# BEP2_rev1.net
KiCad netlist of a schematic drawn in EAGLE
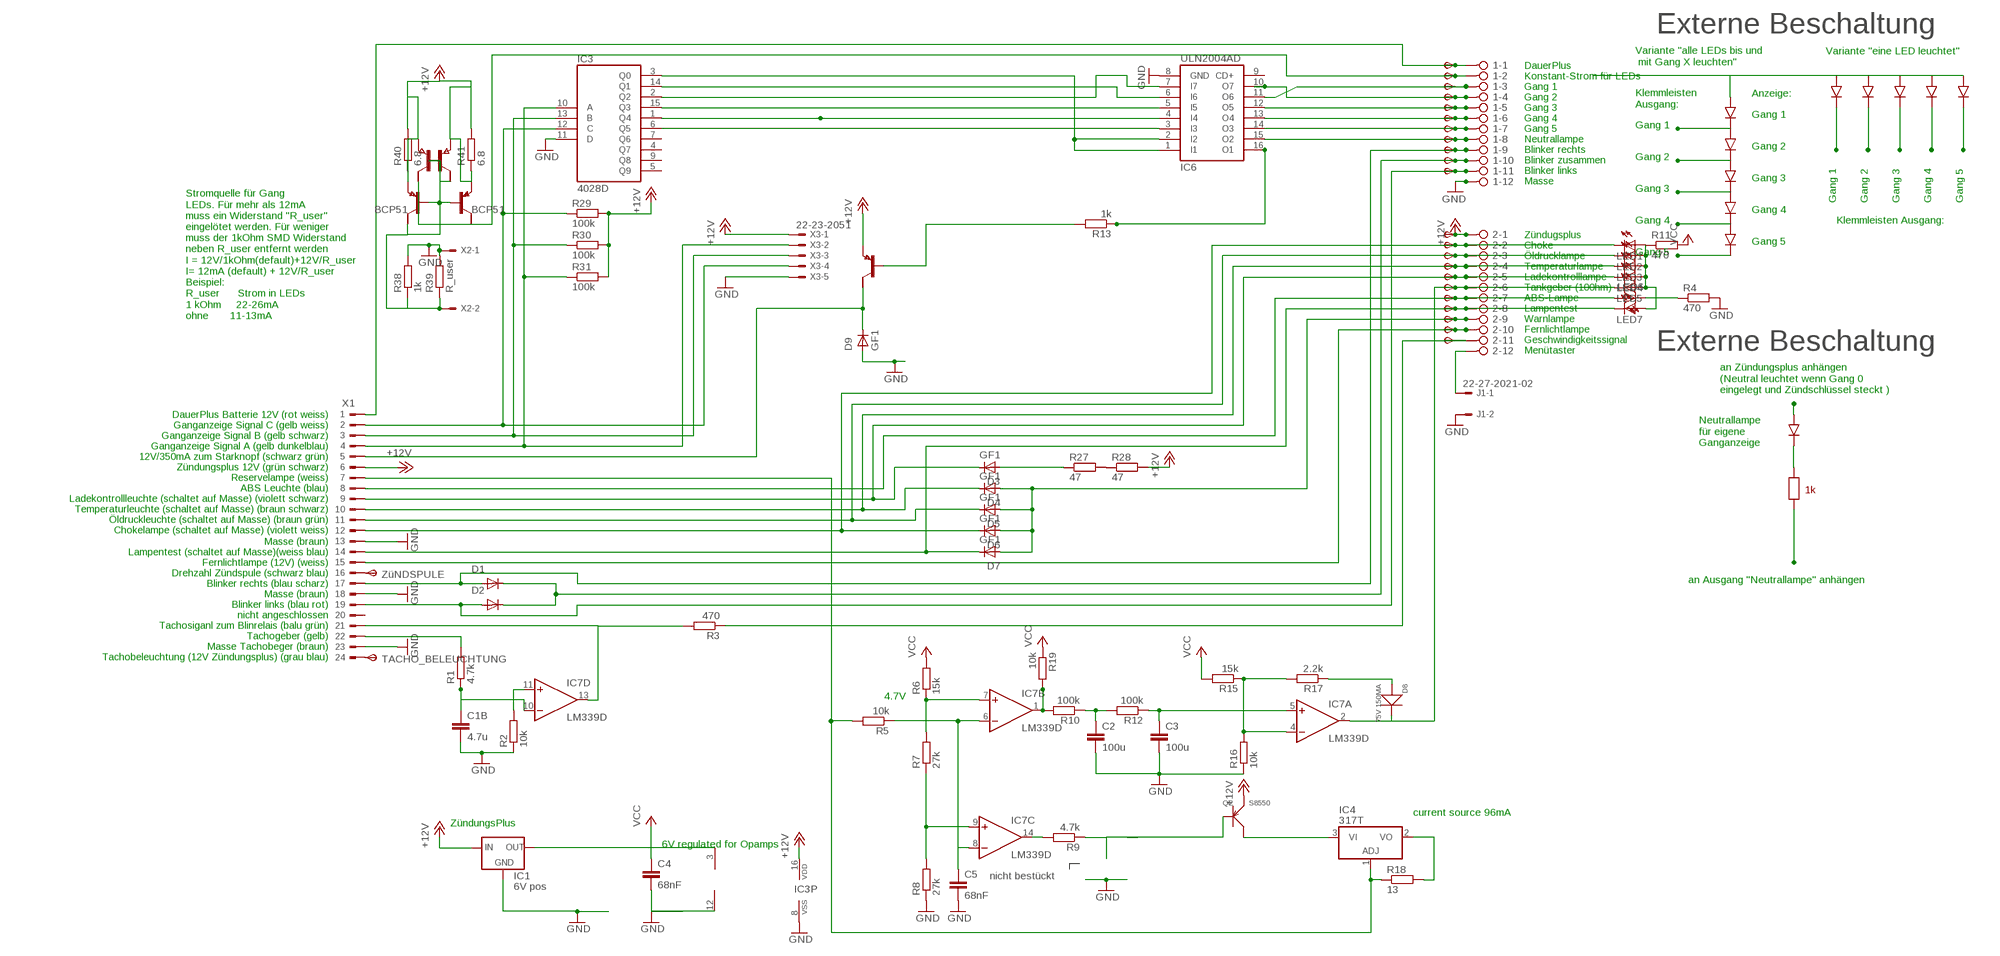
[diagram p0: schematic, sheet 1]

(export (version "E")
  (design (tool "Eeschema 10.0.6"))
  (components
    (comp (ref "1")
      (value "2081-1132")
      (footprint "eagle-import:12-PIN")
      (libsource (lib "eagle-import") (part "2081-1132"))
    )
    (comp (ref "2")
      (value "2081-1132")
      (footprint "eagle-import:12-PIN")
      (libsource (lib "eagle-import") (part "2081-1132"))
    )
    (comp (ref "C1B")
      (value "4.7u")
      (footprint "eagle-import:C0805K")
      (libsource (lib "eagle-import") (part "C-EUC0805K"))
    )
    (comp (ref "C2")
      (value "100u")
      (footprint "eagle-import:C1206K")
      (libsource (lib "eagle-import") (part "C-EUC1206K"))
    )
    (comp (ref "C3")
      (value "100u")
      (footprint "eagle-import:C1206K")
      (libsource (lib "eagle-import") (part "C-EUC1206K"))
    )
    (comp (ref "C4")
      (value "68nF")
      (footprint "eagle-import:C1206K")
      (libsource (lib "eagle-import") (part "C-EUC1206K"))
    )
    (comp (ref "C5")
      (value "68nF")
      (footprint "eagle-import:C1206K")
      (libsource (lib "eagle-import") (part "C-EUC1206K"))
    )
    (comp (ref "D1")
      (value "GF1")
      (footprint "eagle-import:SMA-DO214AC")
      (libsource (lib "eagle-import") (part "GF1"))
    )
    (comp (ref "D2")
      (value "GF1")
      (footprint "eagle-import:SMA-DO214AC")
      (libsource (lib "eagle-import") (part "GF1"))
    )
    (comp (ref "D3")
      (value "GF1")
      (footprint "eagle-import:SMA-DO214AC")
      (libsource (lib "eagle-import") (part "GF1"))
    )
    (comp (ref "D4")
      (value "GF1")
      (footprint "eagle-import:SMA-DO214AC")
      (libsource (lib "eagle-import") (part "GF1"))
    )
    (comp (ref "D5")
      (value "GF1")
      (footprint "eagle-import:SMA-DO214AC")
      (libsource (lib "eagle-import") (part "GF1"))
    )
    (comp (ref "D6")
      (value "GF1")
      (footprint "eagle-import:SMA-DO214AC")
      (libsource (lib "eagle-import") (part "GF1"))
    )
    (comp (ref "D7")
      (value "GF1")
      (footprint "eagle-import:SMA-DO214AC")
      (libsource (lib "eagle-import") (part "GF1"))
    )
    (comp (ref "D8")
      (value "75V 150MA")
      (footprint "eagle-import:LED-1206")
      (fields (field (name "MPN") "CD1206-S01575"))
      (libsource (lib "eagle-import") (part "SMD-DIODE-SWITCHING-75V-150MA(D1206)"))
    )
    (comp (ref "D9")
      (value "GF1")
      (footprint "eagle-import:SMA-DO214AC")
      (libsource (lib "eagle-import") (part "GF1"))
    )
    (comp (ref "IC1")
      (value "6V pos")
      (footprint "eagle-import:78LXX")
      (libsource (lib "eagle-import") (part "78LXX"))
    )
    (comp (ref "IC3")
      (value "4028D")
      (footprint "eagle-import:SO16")
      (libsource (lib "eagle-import") (part "4028D"))
    )
    (comp (ref "IC4")
      (value "317T")
      (footprint "eagle-import:TO220H")
      (libsource (lib "eagle-import") (part "317T"))
    )
    (comp (ref "IC6")
      (value "ULN2004AD")
      (footprint "eagle-import:SO16")
      (libsource (lib "eagle-import") (part "ULN2004AD"))
    )
    (comp (ref "IC7")
      (value "LM339D")
      (footprint "eagle-import:SO14")
      (libsource (lib "eagle-import") (part "LM339D"))
    )
    (comp (ref "J1")
      (value "22-27-2021-02")
      (footprint "eagle-import:6410-02")
      (libsource (lib "eagle-import") (part "22-?-0227-2021"))
    )
    (comp (ref "LED1")
      (value "LEDLD260")
      (footprint "eagle-import:LD260")
      (libsource (lib "eagle-import") (part "LEDLD260"))
    )
    (comp (ref "LED2")
      (value "LEDLD260")
      (footprint "eagle-import:LD260")
      (libsource (lib "eagle-import") (part "LEDLD260"))
    )
    (comp (ref "LED3")
      (value "LEDLD260")
      (footprint "eagle-import:LD260")
      (libsource (lib "eagle-import") (part "LEDLD260"))
    )
    (comp (ref "LED4")
      (value "LEDLD260")
      (footprint "eagle-import:LD260")
      (libsource (lib "eagle-import") (part "LEDLD260"))
    )
    (comp (ref "LED5")
      (value "LEDLD260")
      (footprint "eagle-import:LD260")
      (libsource (lib "eagle-import") (part "LEDLD260"))
    )
    (comp (ref "LED6")
      (value "LEDLD260")
      (footprint "eagle-import:LD260")
      (libsource (lib "eagle-import") (part "LEDLD260"))
    )
    (comp (ref "LED7")
      (value "LEDLD260")
      (footprint "eagle-import:LD260")
      (libsource (lib "eagle-import") (part "LEDLD260"))
    )
    (comp (ref "Q2")
      (value "S8550")
      (footprint "eagle-import:SOT-23")
      (libsource (lib "eagle-import") (part "SMD-TRANSISTORS-PNP-25V-500MA-S8550(SOT-23)"))
    )
    (comp (ref "Q3")
      (value "BCP53T1")
      (footprint "eagle-import:SOT223")
      (libsource (lib "eagle-import") (part "BCP53T1"))
    )
    (comp (ref "R1")
      (value "4.7k")
      (footprint "eagle-import:R0805")
      (libsource (lib "eagle-import") (part "R-EU_R0805"))
    )
    (comp (ref "R2")
      (value "10k")
      (footprint "eagle-import:R0805")
      (libsource (lib "eagle-import") (part "R-EU_R0805"))
    )
    (comp (ref "R3")
      (value "470")
      (footprint "eagle-import:R0805")
      (libsource (lib "eagle-import") (part "R-EU_R0805"))
    )
    (comp (ref "R4")
      (value "470")
      (footprint "eagle-import:R0805")
      (libsource (lib "eagle-import") (part "R-EU_R0805"))
    )
    (comp (ref "R5")
      (value "10k")
      (footprint "eagle-import:R0805")
      (libsource (lib "eagle-import") (part "R-EU_R0805"))
    )
    (comp (ref "R6")
      (value "15k")
      (footprint "eagle-import:R0805")
      (libsource (lib "eagle-import") (part "R-EU_R0805"))
    )
    (comp (ref "R7")
      (value "27k")
      (footprint "eagle-import:R0805")
      (libsource (lib "eagle-import") (part "R-EU_R0805"))
    )
    (comp (ref "R8")
      (value "27k")
      (footprint "eagle-import:R0805")
      (libsource (lib "eagle-import") (part "R-EU_R0805"))
    )
    (comp (ref "R9")
      (value "4.7k")
      (footprint "eagle-import:R0805")
      (libsource (lib "eagle-import") (part "R-EU_R0805"))
    )
    (comp (ref "R10")
      (value "100k")
      (footprint "eagle-import:R0805")
      (libsource (lib "eagle-import") (part "R-EU_R0805"))
    )
    (comp (ref "R11")
      (value "470")
      (footprint "eagle-import:R0805")
      (libsource (lib "eagle-import") (part "R-EU_R0805"))
    )
    (comp (ref "R12")
      (value "100k")
      (footprint "eagle-import:R0805")
      (libsource (lib "eagle-import") (part "R-EU_R0805"))
    )
    (comp (ref "R13")
      (value "1k")
      (footprint "eagle-import:R0805")
      (libsource (lib "eagle-import") (part "R-EU_R0805"))
    )
    (comp (ref "R15")
      (value "15k")
      (footprint "eagle-import:R0805")
      (libsource (lib "eagle-import") (part "R-EU_R0805"))
    )
    (comp (ref "R16")
      (value "10k")
      (footprint "eagle-import:R0805")
      (libsource (lib "eagle-import") (part "R-EU_R0805"))
    )
    (comp (ref "R17")
      (value "2.2k")
      (footprint "eagle-import:R0805")
      (libsource (lib "eagle-import") (part "R-EU_R0805"))
    )
    (comp (ref "R18")
      (value "13")
      (footprint "eagle-import:R1206")
      (libsource (lib "eagle-import") (part "R-EU_R1206"))
    )
    (comp (ref "R19")
      (value "10k")
      (footprint "eagle-import:R0805")
      (libsource (lib "eagle-import") (part "R-EU_R0805"))
    )
    (comp (ref "R27")
      (value "47")
      (footprint "eagle-import:V235_17_1MM")
      (libsource (lib "eagle-import") (part "R-EU_V235/17_1MM"))
    )
    (comp (ref "R28")
      (value "47")
      (footprint "eagle-import:V235_17_1MM")
      (libsource (lib "eagle-import") (part "R-EU_V235/17_1MM"))
    )
    (comp (ref "R29")
      (value "100k")
      (footprint "eagle-import:R0805")
      (libsource (lib "eagle-import") (part "R-EU_R0805"))
    )
    (comp (ref "R30")
      (value "100k")
      (footprint "eagle-import:R0805")
      (libsource (lib "eagle-import") (part "R-EU_R0805"))
    )
    (comp (ref "R31")
      (value "100k")
      (footprint "eagle-import:R0805")
      (libsource (lib "eagle-import") (part "R-EU_R0805"))
    )
    (comp (ref "R38")
      (value "1k")
      (footprint "eagle-import:R0805")
      (libsource (lib "eagle-import") (part "R-EU_R0805"))
    )
    (comp (ref "R39")
      (value "R_user")
      (footprint "eagle-import:R0805")
      (libsource (lib "eagle-import") (part "R-EU_R0805"))
    )
    (comp (ref "R40")
      (value "6.8")
      (footprint "eagle-import:R0805")
      (libsource (lib "eagle-import") (part "R-EU_R0805"))
    )
    (comp (ref "R41")
      (value "6.8")
      (footprint "eagle-import:R0805")
      (libsource (lib "eagle-import") (part "R-EU_R0805"))
    )
    (comp (ref "T1")
      (value "PNP2SM8")
      (footprint "eagle-import:SM8")
      (libsource (lib "eagle-import") (part "PNP2SM8"))
    )
    (comp (ref "T13")
      (value "BCP53T1")
      (footprint "eagle-import:SOT223")
      (fields (field (name "T") "BCP51"))
      (libsource (lib "eagle-import") (part "BCP53T1"))
    )
    (comp (ref "T14")
      (value "BCP53T1")
      (footprint "eagle-import:SOT223")
      (fields (field (name "T") "BCP51"))
      (libsource (lib "eagle-import") (part "BCP53T1"))
    )
    (comp (ref "TACHO_BELEUCHTUNG")
      (value "TPSP1_1MM")
      (footprint "eagle-import:P1_1.0MM")
      (libsource (lib "eagle-import") (part "TPSP1_1MM"))
    )
    (comp (ref "TP1")
      (value "TPSB1,27")
      (footprint "eagle-import:B1,27")
      (libsource (lib "eagle-import") (part "TPSB1,27"))
    )
    (comp (ref "TP2")
      (value "TPSB1,27")
      (footprint "eagle-import:B1,27")
      (libsource (lib "eagle-import") (part "TPSB1,27"))
    )
    (comp (ref "TP3")
      (value "TPSB1,27")
      (footprint "eagle-import:B1,27")
      (libsource (lib "eagle-import") (part "TPSB1,27"))
    )
    (comp (ref "TP4")
      (value "TPSB1,27")
      (footprint "eagle-import:B1,27")
      (libsource (lib "eagle-import") (part "TPSB1,27"))
    )
    (comp (ref "TP5")
      (value "TPSB1,27")
      (footprint "eagle-import:B1,27")
      (libsource (lib "eagle-import") (part "TPSB1,27"))
    )
    (comp (ref "TP6")
      (value "TPSB1,27")
      (footprint "eagle-import:B1,27")
      (libsource (lib "eagle-import") (part "TPSB1,27"))
    )
    (comp (ref "TP7")
      (value "TPSB1,27")
      (footprint "eagle-import:B1,27")
      (libsource (lib "eagle-import") (part "TPSB1,27"))
    )
    (comp (ref "TP8")
      (value "TPSB1,27")
      (footprint "eagle-import:B1,27")
      (libsource (lib "eagle-import") (part "TPSB1,27"))
    )
    (comp (ref "TP9")
      (value "TPSB1,27")
      (footprint "eagle-import:B1,27")
      (libsource (lib "eagle-import") (part "TPSB1,27"))
    )
    (comp (ref "TP10")
      (value "TPSB1,27")
      (footprint "eagle-import:B1,27")
      (libsource (lib "eagle-import") (part "TPSB1,27"))
    )
    (comp (ref "TP11")
      (value "TPSB1,27")
      (footprint "eagle-import:B1,27")
      (libsource (lib "eagle-import") (part "TPSB1,27"))
    )
    (comp (ref "TP12")
      (value "TPSB1,27")
      (footprint "eagle-import:B1,27")
      (libsource (lib "eagle-import") (part "TPSB1,27"))
    )
    (comp (ref "TP16")
      (value "TPSB1,27")
      (footprint "eagle-import:B1,27")
      (libsource (lib "eagle-import") (part "TPSB1,27"))
    )
    (comp (ref "TP17")
      (value "TPSB1,27")
      (footprint "eagle-import:B1,27")
      (libsource (lib "eagle-import") (part "TPSB1,27"))
    )
    (comp (ref "TP18")
      (value "TPSB1,27")
      (footprint "eagle-import:B1,27")
      (libsource (lib "eagle-import") (part "TPSB1,27"))
    )
    (comp (ref "TP19")
      (value "TPSB1,27")
      (footprint "eagle-import:B1,27")
      (libsource (lib "eagle-import") (part "TPSB1,27"))
    )
    (comp (ref "TP21")
      (value "TPSB1,27")
      (footprint "eagle-import:B1,27")
      (libsource (lib "eagle-import") (part "TPSB1,27"))
    )
    (comp (ref "TP22")
      (value "TPSB1,27")
      (footprint "eagle-import:B1,27")
      (libsource (lib "eagle-import") (part "TPSB1,27"))
    )
    (comp (ref "TP23")
      (value "TPSB1,27")
      (footprint "eagle-import:B1,27")
      (libsource (lib "eagle-import") (part "TPSB1,27"))
    )
    (comp (ref "TP24")
      (value "TPSB1,27")
      (footprint "eagle-import:B1,27")
      (libsource (lib "eagle-import") (part "TPSB1,27"))
    )
    (comp (ref "TP25")
      (value "TPSB1,27")
      (footprint "eagle-import:B1,27")
      (libsource (lib "eagle-import") (part "TPSB1,27"))
    )
    (comp (ref "TP26")
      (value "TPSB1,27")
      (footprint "eagle-import:B1,27")
      (libsource (lib "eagle-import") (part "TPSB1,27"))
    )
    (comp (ref "X1")
      (value "CON_BMW")
      (footprint "eagle-import:24-PIN")
      (libsource (lib "eagle-import") (part "CON_BMW"))
    )
    (comp (ref "X2")
      (value "22-23-2021")
      (footprint "eagle-import:22-23-2021")
      (fields (field (name "MF") "MOLEX"))
      (libsource (lib "eagle-import") (part "22-23-2021"))
    )
    (comp (ref "X3")
      (value "22-23-2051")
      (footprint "eagle-import:22-23-2051")
      (fields (field (name "MF") "MOLEX"))
      (libsource (lib "eagle-import") (part "22-23-2051"))
    )
    (comp (ref "ZüNDSPULE")
      (value "TPSP1_1MM")
      (footprint "eagle-import:P1_1.0MM")
      (libsource (lib "eagle-import") (part "TPSP1_1MM"))
    )
  )
  (nets
    (net (code "1") (name "+12V") (class "Default")
      (node (ref "2") (pin "1") (pinfunction "KL_1") (pintype "passive"))
      (node (ref "IC1") (pin "IN") (pinfunction "IN_IN") (pintype "input"))
      (node (ref "IC3") (pin "16") (pinfunction "VDD_16") (pintype "power_in"))
      (node (ref "Q2") (pin "2") (pinfunction "E_2") (pintype "passive"))
      (node (ref "Q3") (pin "3") (pinfunction "E_3") (pintype "passive"))
      (node (ref "R28") (pin "2") (pinfunction "2_2") (pintype "passive"))
      (node (ref "R29") (pin "2") (pinfunction "2_2") (pintype "passive"))
      (node (ref "R30") (pin "2") (pinfunction "2_2") (pintype "passive"))
      (node (ref "R31") (pin "2") (pinfunction "2_2") (pintype "passive"))
      (node (ref "R40") (pin "1") (pinfunction "1_1") (pintype "passive"))
      (node (ref "R40") (pin "2") (pinfunction "2_2") (pintype "passive"))
      (node (ref "R41") (pin "1") (pinfunction "1_1") (pintype "passive"))
      (node (ref "R41") (pin "2") (pinfunction "2_2") (pintype "passive"))
      (node (ref "T1") (pin "1") (pinfunction "E_1") (pintype "passive"))
      (node (ref "T1") (pin "3") (pinfunction "E_3") (pintype "passive"))
      (node (ref "T13") (pin "3") (pinfunction "E_3") (pintype "passive"))
      (node (ref "T14") (pin "3") (pinfunction "E_3") (pintype "passive"))
      (node (ref "TP12") (pin "TP") (pinfunction "PP_TP") (pintype "input"))
      (node (ref "X1") (pin "6") (pinfunction "6_6") (pintype "passive"))
      (node (ref "X3") (pin "1") (pinfunction "S_1") (pintype "passive"))
    )
    (net (code "2") (name "GND") (class "Default")
      (node (ref "1") (pin "12") (pinfunction "KL_12") (pintype "passive"))
      (node (ref "C1B") (pin "2") (pinfunction "2_2") (pintype "passive"))
      (node (ref "C2") (pin "2") (pinfunction "2_2") (pintype "passive"))
      (node (ref "C3") (pin "2") (pinfunction "2_2") (pintype "passive"))
      (node (ref "C4") (pin "2") (pinfunction "2_2") (pintype "passive"))
      (node (ref "C5") (pin "2") (pinfunction "2_2") (pintype "passive"))
      (node (ref "D9") (pin "A") (pinfunction "A_A") (pintype "passive"))
      (node (ref "IC1") (pin "GND") (pinfunction "GND_GND") (pintype "input"))
      (node (ref "IC3") (pin "11") (pinfunction "D_11") (pintype "input"))
      (node (ref "IC3") (pin "8") (pinfunction "VSS_8") (pintype "power_in"))
      (node (ref "IC6") (pin "8") (pinfunction "GND_8") (pintype "power_in"))
      (node (ref "IC7") (pin "12") (pinfunction "GND_12") (pintype "power_in"))
      (node (ref "J1") (pin "2") (pinfunction "S_2") (pintype "passive"))
      (node (ref "R16") (pin "1") (pinfunction "1_1") (pintype "passive"))
      (node (ref "R2") (pin "1") (pinfunction "1_1") (pintype "passive"))
      (node (ref "R38") (pin "2") (pinfunction "2_2") (pintype "passive"))
      (node (ref "R39") (pin "2") (pinfunction "2_2") (pintype "passive"))
      (node (ref "R4") (pin "2") (pinfunction "2_2") (pintype "passive"))
      (node (ref "R8") (pin "1") (pinfunction "1_1") (pintype "passive"))
      (node (ref "X1") (pin "13") (pinfunction "13_13") (pintype "passive"))
      (node (ref "X1") (pin "18") (pinfunction "18_18") (pintype "passive"))
      (node (ref "X1") (pin "23") (pinfunction "23_23") (pintype "passive"))
      (node (ref "X2") (pin "1") (pinfunction "S_1") (pintype "passive"))
      (node (ref "X3") (pin "5") (pinfunction "S_5") (pintype "passive"))
    )
    (net (code "3") (name "Net-(1A-KL)") (class "Default")
      (node (ref "1") (pin "1") (pinfunction "KL_1") (pintype "passive"))
      (node (ref "TP1") (pin "TP") (pinfunction "PP_TP") (pintype "input"))
      (node (ref "X1") (pin "1") (pinfunction "1_1") (pintype "passive"))
    )
    (net (code "4") (name "Net-(1B-KL)") (class "Default")
      (node (ref "1") (pin "10") (pinfunction "KL_10") (pintype "passive"))
      (node (ref "D1") (pin "K") (pinfunction "C_K") (pintype "passive"))
      (node (ref "D2") (pin "K") (pinfunction "C_K") (pintype "passive"))
      (node (ref "TP10") (pin "TP") (pinfunction "PP_TP") (pintype "input"))
    )
    (net (code "5") (name "Net-(1C-KL)") (class "Default")
      (node (ref "1") (pin "11") (pinfunction "KL_11") (pintype "passive"))
      (node (ref "D2") (pin "A") (pinfunction "A_A") (pintype "passive"))
      (node (ref "TP11") (pin "TP") (pinfunction "PP_TP") (pintype "input"))
      (node (ref "X1") (pin "19") (pinfunction "19_19") (pintype "passive"))
    )
    (net (code "6") (name "Net-(1E-KL)") (class "Default")
      (node (ref "1") (pin "2") (pinfunction "KL_2") (pintype "passive"))
      (node (ref "T1") (pin "8") (pinfunction "C1_8") (pintype "passive"))
      (node (ref "T14") (pin "2") (pinfunction "C_2") (pintype "passive"))
      (node (ref "TP2") (pin "TP") (pinfunction "PP_TP") (pintype "input"))
    )
    (net (code "7") (name "Net-(1F-KL)") (class "Default")
      (node (ref "1") (pin "3") (pinfunction "KL_3") (pintype "passive"))
      (node (ref "IC6") (pin "11") (pinfunction "O6_11") (pintype "open_collector"))
      (node (ref "TP3") (pin "TP") (pinfunction "PP_TP") (pintype "input"))
    )
    (net (code "8") (name "Net-(1G-KL)") (class "Default")
      (node (ref "1") (pin "4") (pinfunction "KL_4") (pintype "passive"))
      (node (ref "IC6") (pin "10") (pinfunction "O7_10") (pintype "open_collector"))
      (node (ref "TP4") (pin "TP") (pinfunction "PP_TP") (pintype "input"))
    )
    (net (code "9") (name "Net-(1H-KL)") (class "Default")
      (node (ref "1") (pin "5") (pinfunction "KL_5") (pintype "passive"))
      (node (ref "IC6") (pin "12") (pinfunction "O5_12") (pintype "open_collector"))
      (node (ref "TP5") (pin "TP") (pinfunction "PP_TP") (pintype "input"))
    )
    (net (code "10") (name "Net-(1I-KL)") (class "Default")
      (node (ref "1") (pin "6") (pinfunction "KL_6") (pintype "passive"))
      (node (ref "IC6") (pin "13") (pinfunction "O4_13") (pintype "open_collector"))
      (node (ref "TP6") (pin "TP") (pinfunction "PP_TP") (pintype "input"))
    )
    (net (code "11") (name "Net-(1J-KL)") (class "Default")
      (node (ref "1") (pin "7") (pinfunction "KL_7") (pintype "passive"))
      (node (ref "IC6") (pin "14") (pinfunction "O3_14") (pintype "open_collector"))
      (node (ref "TP7") (pin "TP") (pinfunction "PP_TP") (pintype "input"))
    )
    (net (code "12") (name "Net-(1K-KL)") (class "Default")
      (node (ref "1") (pin "8") (pinfunction "KL_8") (pintype "passive"))
      (node (ref "IC6") (pin "15") (pinfunction "O2_15") (pintype "open_collector"))
      (node (ref "TP8") (pin "TP") (pinfunction "PP_TP") (pintype "input"))
    )
    (net (code "13") (name "Net-(1L-KL)") (class "Default")
      (node (ref "1") (pin "9") (pinfunction "KL_9") (pintype "passive"))
      (node (ref "D1") (pin "A") (pinfunction "A_A") (pintype "passive"))
      (node (ref "TP9") (pin "TP") (pinfunction "PP_TP") (pintype "input"))
      (node (ref "X1") (pin "17") (pinfunction "17_17") (pintype "passive"))
    )
    (net (code "14") (name "Net-(2B-KL)") (class "Default")
      (node (ref "2") (pin "10") (pinfunction "KL_10") (pintype "passive"))
      (node (ref "TP25") (pin "TP") (pinfunction "PP_TP") (pintype "input"))
      (node (ref "X1") (pin "15") (pinfunction "15_15") (pintype "passive"))
    )
    (net (code "15") (name "Net-(2C-KL)") (class "Default")
      (node (ref "2") (pin "11") (pinfunction "KL_11") (pintype "passive"))
      (node (ref "R3") (pin "1") (pinfunction "1_1") (pintype "passive"))
      (node (ref "TP26") (pin "TP") (pinfunction "PP_TP") (pintype "input"))
    )
    (net (code "16") (name "Net-(2D-KL)") (class "Default")
      (node (ref "2") (pin "12") (pinfunction "KL_12") (pintype "passive"))
      (node (ref "J1") (pin "1") (pinfunction "S_1") (pintype "passive"))
    )
    (net (code "17") (name "Net-(2E-KL)") (class "Default")
      (node (ref "2") (pin "2") (pinfunction "KL_2") (pintype "passive"))
      (node (ref "D6") (pin "K") (pinfunction "C_K") (pintype "passive"))
      (node (ref "LED1") (pin "K") (pinfunction "C_K") (pintype "passive"))
      (node (ref "TP16") (pin "TP") (pinfunction "PP_TP") (pintype "input"))
      (node (ref "X1") (pin "12") (pinfunction "12_12") (pintype "passive"))
    )
    (net (code "18") (name "Net-(2F-KL)") (class "Default")
      (node (ref "2") (pin "3") (pinfunction "KL_3") (pintype "passive"))
      (node (ref "D5") (pin "K") (pinfunction "C_K") (pintype "passive"))
      (node (ref "LED2") (pin "K") (pinfunction "C_K") (pintype "passive"))
      (node (ref "TP17") (pin "TP") (pinfunction "PP_TP") (pintype "input"))
      (node (ref "X1") (pin "11") (pinfunction "11_11") (pintype "passive"))
    )
    (net (code "19") (name "Net-(2G-KL)") (class "Default")
      (node (ref "2") (pin "4") (pinfunction "KL_4") (pintype "passive"))
      (node (ref "D4") (pin "K") (pinfunction "C_K") (pintype "passive"))
      (node (ref "LED3") (pin "K") (pinfunction "C_K") (pintype "passive"))
      (node (ref "TP18") (pin "TP") (pinfunction "PP_TP") (pintype "input"))
      (node (ref "X1") (pin "10") (pinfunction "10_10") (pintype "passive"))
    )
    (net (code "20") (name "Net-(2H-KL)") (class "Default")
      (node (ref "2") (pin "5") (pinfunction "KL_5") (pintype "passive"))
      (node (ref "D3") (pin "K") (pinfunction "C_K") (pintype "passive"))
      (node (ref "LED4") (pin "K") (pinfunction "C_K") (pintype "passive"))
      (node (ref "TP19") (pin "TP") (pinfunction "PP_TP") (pintype "input"))
      (node (ref "X1") (pin "9") (pinfunction "9_9") (pintype "passive"))
    )
    (net (code "21") (name "Net-(2I-KL)") (class "Default")
      (node (ref "2") (pin "6") (pinfunction "KL_6") (pintype "passive"))
      (node (ref "D8") (pin "-") (pinfunction "-_-") (pintype "passive"))
      (node (ref "IC7") (pin "2") (pinfunction "OUT_2") (pintype "open_collector"))
      (node (ref "LED5") (pin "K") (pinfunction "C_K") (pintype "passive"))
      (node (ref "TP21") (pin "TP") (pinfunction "PP_TP") (pintype "input"))
    )
    (net (code "22") (name "Net-(2J-KL)") (class "Default")
      (node (ref "2") (pin "7") (pinfunction "KL_7") (pintype "passive"))
      (node (ref "LED6") (pin "A") (pinfunction "A_A") (pintype "passive"))
      (node (ref "TP22") (pin "TP") (pinfunction "PP_TP") (pintype "input"))
      (node (ref "X1") (pin "8") (pinfunction "8_8") (pintype "passive"))
    )
    (net (code "23") (name "Net-(2K-KL)") (class "Default")
      (node (ref "2") (pin "8") (pinfunction "KL_8") (pintype "passive"))
      (node (ref "D7") (pin "K") (pinfunction "C_K") (pintype "passive"))
      (node (ref "LED7") (pin "K") (pinfunction "C_K") (pintype "passive"))
      (node (ref "TP23") (pin "TP") (pinfunction "PP_TP") (pintype "input"))
      (node (ref "X1") (pin "14") (pinfunction "14_14") (pintype "passive"))
    )
    (net (code "24") (name "Net-(2L-KL)") (class "Default")
      (node (ref "2") (pin "9") (pinfunction "KL_9") (pintype "passive"))
      (node (ref "D4") (pin "A") (pinfunction "A_A") (pintype "passive"))
      (node (ref "D5") (pin "A") (pinfunction "A_A") (pintype "passive"))
      (node (ref "D6") (pin "A") (pinfunction "A_A") (pintype "passive"))
      (node (ref "D7") (pin "A") (pinfunction "A_A") (pintype "passive"))
      (node (ref "TP24") (pin "TP") (pinfunction "PP_TP") (pintype "input"))
    )
    (net (code "25") (name "Net-(C2-Pad1)") (class "Default")
      (node (ref "C2") (pin "1") (pinfunction "1_1") (pintype "passive"))
      (node (ref "R10") (pin "1") (pinfunction "1_1") (pintype "passive"))
      (node (ref "R12") (pin "2") (pinfunction "2_2") (pintype "passive"))
    )
    (net (code "26") (name "Net-(D3-PadA)") (class "Default")
      (node (ref "D3") (pin "A") (pinfunction "A_A") (pintype "passive"))
      (node (ref "R27") (pin "1") (pinfunction "1_1") (pintype "passive"))
    )
    (net (code "27") (name "Net-(D8-Pad+)") (class "Default")
      (node (ref "D8") (pin "+") (pinfunction "+_+") (pintype "passive"))
      (node (ref "R17") (pin "1") (pinfunction "1_1") (pintype "passive"))
    )
    (net (code "28") (name "Net-(D9-C)") (class "Default")
      (node (ref "D9") (pin "K") (pinfunction "C_K") (pintype "passive"))
      (node (ref "Q3") (pin "2") (pinfunction "C_2") (pintype "passive"))
      (node (ref "X1") (pin "5") (pinfunction "5_5") (pintype "passive"))
    )
    (net (code "29") (name "Net-(IC3A-A)") (class "Default")
      (node (ref "IC3") (pin "10") (pinfunction "A_10") (pintype "input"))
      (node (ref "R31") (pin "1") (pinfunction "1_1") (pintype "passive"))
      (node (ref "X1") (pin "4") (pinfunction "4_4") (pintype "passive"))
      (node (ref "X3") (pin "2") (pinfunction "S_2") (pintype "passive"))
    )
    (net (code "30") (name "Net-(IC3A-B)") (class "Default")
      (node (ref "IC3") (pin "13") (pinfunction "B_13") (pintype "input"))
      (node (ref "R30") (pin "1") (pinfunction "1_1") (pintype "passive"))
      (node (ref "X1") (pin "3") (pinfunction "3_3") (pintype "passive"))
      (node (ref "X3") (pin "3") (pinfunction "S_3") (pintype "passive"))
    )
    (net (code "31") (name "Net-(IC3A-C)") (class "Default")
      (node (ref "IC3") (pin "12") (pinfunction "C_12") (pintype "input"))
      (node (ref "R29") (pin "1") (pinfunction "1_1") (pintype "passive"))
      (node (ref "X1") (pin "2") (pinfunction "2_2") (pintype "passive"))
      (node (ref "X3") (pin "4") (pinfunction "S_4") (pintype "passive"))
    )
    (net (code "32") (name "Net-(IC3A-Q0)") (class "Default")
      (node (ref "IC3") (pin "3") (pinfunction "Q0_3") (pintype "output"))
      (node (ref "IC6") (pin "1") (pinfunction "I1_1") (pintype "input"))
      (node (ref "IC6") (pin "2") (pinfunction "I2_2") (pintype "input"))
    )
    (net (code "33") (name "Net-(IC3A-Q1)") (class "Default")
      (node (ref "IC3") (pin "14") (pinfunction "Q1_14") (pintype "output"))
      (node (ref "IC6") (pin "6") (pinfunction "I6_6") (pintype "input"))
    )
    (net (code "34") (name "Net-(IC3A-Q2)") (class "Default")
      (node (ref "IC3") (pin "2") (pinfunction "Q2_2") (pintype "output"))
      (node (ref "IC6") (pin "7") (pinfunction "I7_7") (pintype "input"))
    )
    (net (code "35") (name "Net-(IC3A-Q3)") (class "Default")
      (node (ref "IC3") (pin "15") (pinfunction "Q3_15") (pintype "output"))
      (node (ref "IC6") (pin "5") (pinfunction "I5_5") (pintype "input"))
    )
    (net (code "36") (name "Net-(IC3A-Q4)") (class "Default")
      (node (ref "IC3") (pin "1") (pinfunction "Q4_1") (pintype "output"))
      (node (ref "IC6") (pin "4") (pinfunction "I4_4") (pintype "input"))
    )
    (net (code "37") (name "Net-(IC3A-Q5)") (class "Default")
      (node (ref "IC3") (pin "6") (pinfunction "Q5_6") (pintype "output"))
      (node (ref "IC6") (pin "3") (pinfunction "I3_3") (pintype "input"))
    )
    (net (code "38") (name "Net-(IC4-ADJ)") (class "Default")
      (node (ref "IC4") (pin "1") (pinfunction "ADJ_1") (pintype "input"))
      (node (ref "R18") (pin "1") (pinfunction "1_1") (pintype "passive"))
      (node (ref "R5") (pin "2") (pinfunction "2_2") (pintype "passive"))
      (node (ref "X1") (pin "7") (pinfunction "7_7") (pintype "passive"))
    )
    (net (code "39") (name "Net-(IC4-VI)") (class "Default")
      (node (ref "IC4") (pin "3") (pinfunction "VI_3") (pintype "input"))
      (node (ref "Q2") (pin "3") (pinfunction "C_3") (pintype "passive"))
    )
    (net (code "40") (name "Net-(IC4-VO)") (class "Default")
      (node (ref "IC4") (pin "2") (pinfunction "VO_2") (pintype "passive"))
      (node (ref "R18") (pin "2") (pinfunction "2_2") (pintype "passive"))
    )
    (net (code "41") (name "Net-(IC6-O1)") (class "Default")
      (node (ref "IC6") (pin "16") (pinfunction "O1_16") (pintype "open_collector"))
      (node (ref "R13") (pin "1") (pinfunction "1_1") (pintype "passive"))
    )
    (net (code "42") (name "Net-(IC7A-+IN)") (class "Default")
      (node (ref "C3") (pin "1") (pinfunction "1_1") (pintype "passive"))
      (node (ref "IC7") (pin "5") (pinfunction "+IN_5") (pintype "input"))
      (node (ref "R12") (pin "1") (pinfunction "1_1") (pintype "passive"))
    )
    (net (code "43") (name "Net-(IC7A--IN)") (class "Default")
      (node (ref "IC7") (pin "4") (pinfunction "-IN_4") (pintype "input"))
      (node (ref "R15") (pin "1") (pinfunction "1_1") (pintype "passive"))
      (node (ref "R16") (pin "2") (pinfunction "2_2") (pintype "passive"))
      (node (ref "R17") (pin "2") (pinfunction "2_2") (pintype "passive"))
    )
    (net (code "44") (name "Net-(IC7B-+IN)") (class "Default")
      (node (ref "IC7") (pin "7") (pinfunction "+IN_7") (pintype "input"))
      (node (ref "R6") (pin "1") (pinfunction "1_1") (pintype "passive"))
      (node (ref "R7") (pin "2") (pinfunction "2_2") (pintype "passive"))
    )
    (net (code "45") (name "Net-(IC7B--IN)") (class "Default")
      (node (ref "C5") (pin "1") (pinfunction "1_1") (pintype "passive"))
      (node (ref "IC7") (pin "6") (pinfunction "-IN_6") (pintype "input"))
      (node (ref "IC7") (pin "8") (pinfunction "-IN_8") (pintype "input"))
      (node (ref "R5") (pin "1") (pinfunction "1_1") (pintype "passive"))
    )
    (net (code "46") (name "Net-(IC7B-OUT)") (class "Default")
      (node (ref "IC7") (pin "1") (pinfunction "OUT_1") (pintype "open_collector"))
      (node (ref "R10") (pin "2") (pinfunction "2_2") (pintype "passive"))
      (node (ref "R19") (pin "2") (pinfunction "2_2") (pintype "passive"))
    )
    (net (code "47") (name "Net-(IC7C-+IN)") (class "Default")
      (node (ref "IC7") (pin "9") (pinfunction "+IN_9") (pintype "input"))
      (node (ref "R7") (pin "1") (pinfunction "1_1") (pintype "passive"))
      (node (ref "R8") (pin "2") (pinfunction "2_2") (pintype "passive"))
    )
    (net (code "48") (name "Net-(IC7C-OUT)") (class "Default")
      (node (ref "IC7") (pin "14") (pinfunction "OUT_14") (pintype "open_collector"))
      (node (ref "R9") (pin "2") (pinfunction "2_2") (pintype "passive"))
    )
    (net (code "49") (name "Net-(IC7D-+IN)") (class "Default")
      (node (ref "IC7") (pin "11") (pinfunction "+IN_11") (pintype "input"))
      (node (ref "R2") (pin "2") (pinfunction "2_2") (pintype "passive"))
    )
    (net (code "50") (name "Net-(IC7D--IN)") (class "Default")
      (node (ref "C1B") (pin "1") (pinfunction "1_1") (pintype "passive"))
      (node (ref "IC7") (pin "10") (pinfunction "-IN_10") (pintype "input"))
      (node (ref "R1") (pin "1") (pinfunction "1_1") (pintype "passive"))
    )
    (net (code "51") (name "Net-(IC7D-OUT)") (class "Default")
      (node (ref "IC7") (pin "13") (pinfunction "OUT_13") (pintype "open_collector"))
      (node (ref "R3") (pin "2") (pinfunction "2_2") (pintype "passive"))
      (node (ref "X1") (pin "21") (pinfunction "21_21") (pintype "passive"))
    )
    (net (code "52") (name "Net-(LED1-PadA)") (class "Default")
      (node (ref "LED1") (pin "A") (pinfunction "A_A") (pintype "passive"))
      (node (ref "LED2") (pin "A") (pinfunction "A_A") (pintype "passive"))
      (node (ref "LED3") (pin "A") (pinfunction "A_A") (pintype "passive"))
      (node (ref "LED4") (pin "A") (pinfunction "A_A") (pintype "passive"))
      (node (ref "LED5") (pin "A") (pinfunction "A_A") (pintype "passive"))
      (node (ref "LED7") (pin "A") (pinfunction "A_A") (pintype "passive"))
      (node (ref "R11") (pin "1") (pinfunction "1_1") (pintype "passive"))
    )
    (net (code "53") (name "Net-(LED6-C)") (class "Default")
      (node (ref "LED6") (pin "K") (pinfunction "C_K") (pintype "passive"))
      (node (ref "R4") (pin "1") (pinfunction "1_1") (pintype "passive"))
    )
    (net (code "54") (name "Net-(Q2-B)") (class "Default")
      (node (ref "Q2") (pin "1") (pinfunction "B_1") (pintype "passive"))
      (node (ref "R9") (pin "1") (pinfunction "1_1") (pintype "passive"))
    )
    (net (code "55") (name "Net-(Q3-B)") (class "Default")
      (node (ref "Q3") (pin "1") (pinfunction "B_1") (pintype "passive"))
      (node (ref "R13") (pin "2") (pinfunction "2_2") (pintype "passive"))
    )
    (net (code "56") (name "Net-(R1-Pad2)") (class "Default")
      (node (ref "R1") (pin "2") (pinfunction "2_2") (pintype "passive"))
      (node (ref "X1") (pin "22") (pinfunction "22_22") (pintype "passive"))
    )
    (net (code "57") (name "Net-(R27-Pad2)") (class "Default")
      (node (ref "R27") (pin "2") (pinfunction "2_2") (pintype "passive"))
      (node (ref "R28") (pin "1") (pinfunction "1_1") (pintype "passive"))
    )
    (net (code "58") (name "Net-(T13-B)") (class "Default")
      (node (ref "R38") (pin "1") (pinfunction "1_1") (pintype "passive"))
      (node (ref "R39") (pin "1") (pinfunction "1_1") (pintype "passive"))
      (node (ref "T1") (pin "2") (pinfunction "B_2") (pintype "passive"))
      (node (ref "T1") (pin "4") (pinfunction "B_4") (pintype "passive"))
      (node (ref "T1") (pin "6") (pinfunction "C1_6") (pintype "passive"))
      (node (ref "T13") (pin "1") (pinfunction "B_1") (pintype "passive"))
      (node (ref "T13") (pin "2") (pinfunction "C_2") (pintype "passive"))
      (node (ref "T14") (pin "1") (pinfunction "B_1") (pintype "passive"))
      (node (ref "X2") (pin "2") (pinfunction "S_2") (pintype "passive"))
    )
    (net (code "59") (name "Net-(TACHO_BELEUCHTUNG-PP)") (class "Default")
      (node (ref "TACHO_BELEUCHTUNG") (pin "TP") (pinfunction "PP_TP") (pintype "input"))
      (node (ref "X1") (pin "24") (pinfunction "24_24") (pintype "passive"))
    )
    (net (code "60") (name "Net-(ZüNDSPULE-PP)") (class "Default")
      (node (ref "X1") (pin "16") (pinfunction "16_16") (pintype "passive"))
      (node (ref "ZüNDSPULE") (pin "TP") (pinfunction "PP_TP") (pintype "input"))
    )
    (net (code "61") (name "VCC") (class "Default")
      (node (ref "C4") (pin "1") (pinfunction "1_1") (pintype "passive"))
      (node (ref "IC1") (pin "OUT") (pinfunction "OUT_OUT") (pintype "passive"))
      (node (ref "IC7") (pin "3") (pinfunction "V+_3") (pintype "power_in"))
      (node (ref "R11") (pin "2") (pinfunction "2_2") (pintype "passive"))
      (node (ref "R15") (pin "2") (pinfunction "2_2") (pintype "passive"))
      (node (ref "R19") (pin "1") (pinfunction "1_1") (pintype "passive"))
      (node (ref "R6") (pin "2") (pinfunction "2_2") (pintype "passive"))
    )
    (net (code "62") (name "unconnected-(IC3A-Q6-Pad7)") (class "Default")
      (node (ref "IC3") (pin "7") (pinfunction "Q6_7") (pintype "output"))
    )
    (net (code "63") (name "unconnected-(IC3A-Q7-Pad4)") (class "Default")
      (node (ref "IC3") (pin "4") (pinfunction "Q7_4") (pintype "output"))
    )
    (net (code "64") (name "unconnected-(IC3A-Q8-Pad9)") (class "Default")
      (node (ref "IC3") (pin "9") (pinfunction "Q8_9") (pintype "output"))
    )
    (net (code "65") (name "unconnected-(IC3A-Q9-Pad5)") (class "Default")
      (node (ref "IC3") (pin "5") (pinfunction "Q9_5") (pintype "output"))
    )
    (net (code "66") (name "unconnected-(IC6-CD+-Pad9)") (class "Default")
      (node (ref "IC6") (pin "9") (pinfunction "CD+_9") (pintype "passive"))
    )
    (net (code "67") (name "unconnected-(Q3-C{slash}-Pad4)") (class "Default")
      (node (ref "Q3") (pin "4") (pinfunction "C/_4") (pintype "passive"))
    )
    (net (code "68") (name "unconnected-(T1A-C-Pad5)") (class "Default")
      (node (ref "T1") (pin "5") (pinfunction "C_5") (pintype "passive"))
    )
    (net (code "69") (name "unconnected-(T1B-C-Pad7)") (class "Default")
      (node (ref "T1") (pin "7") (pinfunction "C_7") (pintype "passive"))
    )
    (net (code "70") (name "unconnected-(T13-C{slash}-Pad4)") (class "Default")
      (node (ref "T13") (pin "4") (pinfunction "C/_4") (pintype "passive"))
    )
    (net (code "71") (name "unconnected-(T14-C{slash}-Pad4)") (class "Default")
      (node (ref "T14") (pin "4") (pinfunction "C/_4") (pintype "passive"))
    )
    (net (code "72") (name "unconnected-(X1-Pad20)") (class "Default")
      (node (ref "X1") (pin "20") (pinfunction "20_20") (pintype "passive"))
    )
  )
)
